# SCH_1.net
KiCad netlist of a schematic drawn in Altium Designer
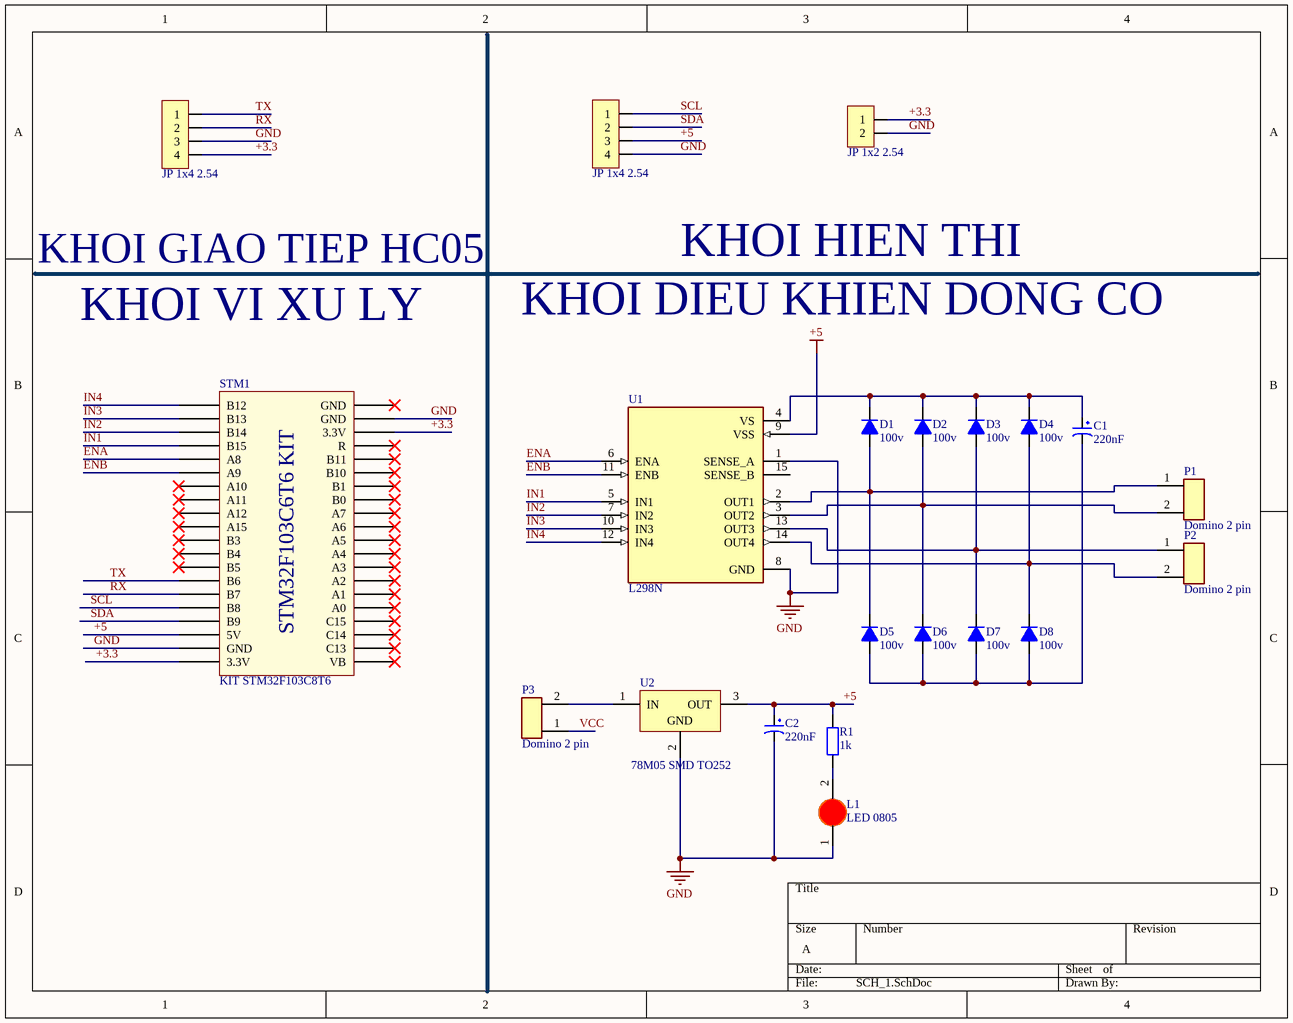
[diagram p0: SCH_1.SchDoc]

(export (version "E")
  (design (tool "Eeschema 10.0.6"))
  (components
    (comp (ref "C1")
      (value "220nF")
      (footprint "tu hoa 8mm")
      (description "Cắm")
      (libsource (lib "Altium_Lib_by_KhueNguyenCreator") (part "Tu Hoa 220uF 35V 8x12"))
    )
    (comp (ref "C2")
      (value "220nF")
      (footprint "tu hoa 8mm")
      (description "Cắm")
      (libsource (lib "Altium_Lib_by_KhueNguyenCreator") (part "Tu Hoa 220uF 35V 8x12"))
    )
    (comp (ref "D1")
      (value "100v")
      (footprint "DIODE 1A")
      (description "Cắm")
      (libsource (lib "Altium_Lib_by_KhueNguyenCreator") (part "Diode 1N4007"))
    )
    (comp (ref "D2")
      (value "100v")
      (footprint "DIODE 1A")
      (description "Cắm")
      (libsource (lib "Altium_Lib_by_KhueNguyenCreator") (part "Diode 1N4007"))
    )
    (comp (ref "D3")
      (value "100v")
      (footprint "DIODE 1A")
      (description "Cắm")
      (libsource (lib "Altium_Lib_by_KhueNguyenCreator") (part "Diode 1N4007"))
    )
    (comp (ref "D4")
      (value "100v")
      (footprint "DIODE 1A")
      (description "Cắm")
      (libsource (lib "Altium_Lib_by_KhueNguyenCreator") (part "Diode 1N4007"))
    )
    (comp (ref "D5")
      (value "100v")
      (footprint "DIODE 1A")
      (description "Cắm")
      (libsource (lib "Altium_Lib_by_KhueNguyenCreator") (part "Diode 1N4007"))
    )
    (comp (ref "D6")
      (value "100v")
      (footprint "DIODE 1A")
      (description "Cắm")
      (libsource (lib "Altium_Lib_by_KhueNguyenCreator") (part "Diode 1N4007"))
    )
    (comp (ref "D7")
      (value "100v")
      (footprint "DIODE 1A")
      (description "Cắm")
      (libsource (lib "Altium_Lib_by_KhueNguyenCreator") (part "Diode 1N4007"))
    )
    (comp (ref "D8")
      (value "100v")
      (footprint "DIODE 1A")
      (description "Cắm")
      (libsource (lib "Altium_Lib_by_KhueNguyenCreator") (part "Diode 1N4007"))
    )
    (comp (ref "JP1")
      (value "JP 1x4 2.54")
      (footprint "JP 1x4 CT")
      (description "Cắm")
      (libsource (lib "Altium_Lib_by_KhueNguyenCreator") (part "JP 1x4 2.54 Cai Thang"))
    )
    (comp (ref "JP2")
      (value "JP 1x4 2.54")
      (footprint "JP 1x4 CC")
      (description "Cắm")
      (libsource (lib "Altium_Lib_by_KhueNguyenCreator") (part "JP 1x4 2.54 Cai Cong"))
    )
    (comp (ref "JP3")
      (value "JP 1x2 2.54")
      (footprint "JP 1x2 DC")
      (description "Cắm")
      (libsource (lib "Altium_Lib_by_KhueNguyenCreator") (part "JP 1x2 2.54 Duc Cong"))
    )
    (comp (ref "L1")
      (value "LED 0805")
      (footprint "LED-0805-Red")
      (description "Dán")
      (libsource (lib "Altium_Lib_by_KhueNguyenCreator") (part "LED 0805 Do"))
    )
    (comp (ref "P1")
      (value "Domino 2 pin")
      (footprint "thuvien_altium:Domino_2pin_5.08mm")
      (description "domino 2 pin")
      (libsource (lib "thuvien_altium") (part "domino_2pin"))
    )
    (comp (ref "P2")
      (value "Domino 2 pin")
      (footprint "thuvien_altium:Domino_2pin_5.08mm")
      (description "domino 2 pin")
      (libsource (lib "thuvien_altium") (part "domino_2pin"))
    )
    (comp (ref "P3")
      (value "Domino 2 pin")
      (footprint "thuvien_altium:Domino_2pin_5.08mm")
      (description "domino 2 pin")
      (libsource (lib "") (part "domino_2pin_1"))
    )
    (comp (ref "R1")
      (value "1k")
      (footprint "tro smd 0805")
      (description "Dán")
      (libsource (lib "Altium_Lib_by_KhueNguyenCreator") (part "Tro 0805 5% 1k"))
    )
    (comp (ref "STM1")
      (value "KIT STM32F103C8T6")
      (footprint "STM32F103 KIT")
      (description "KIT STM32F103C8T6 Bluepill")
      (libsource (lib "Altium_Lib_by_KhueNguyenCreator") (part "STM32f103 Bluepill"))
    )
    (comp (ref "U1")
      (value "L298N")
      (footprint "L298N")
      (description "Half Bridge _4_ Driver DC Motors, Relays, Solenoids, Stepper Motors Bipolar 15-Multiwatt")
      (fields (field (name "MF") "STMicroelectronics"))
      (libsource (lib "Altium_Lib_by_KhueNguyenCreator") (part "L298N"))
    )
    (comp (ref "U2")
      (value "78M05 SMD TO252")
      (footprint "TO252")
      (description "Dán")
      (libsource (lib "Altium_Lib_by_KhueNguyenCreator") (part "78M05 SMD TO252"))
    )
  )
  (nets
    (net (code "1") (name "+5") (class "Default")
      (node (ref "C2") (pin "1") (pinfunction "1_1") (pintype "passive"))
      (node (ref "JP2") (pin "3") (pinfunction "3_3") (pintype "passive"))
      (node (ref "R1") (pin "2") (pinfunction "2_2") (pintype "passive"))
      (node (ref "STM1") (pin "18") (pinfunction "5V_18") (pintype "passive"))
      (node (ref "U1") (pin "9") (pinfunction "VSS_9") (pintype "input"))
      (node (ref "U2") (pin "3") (pinfunction "OUT_3") (pintype "power_in"))
    )
    (net (code "2") (name "/+3.3") (class "Default")
      (node (ref "JP1") (pin "4") (pinfunction "4_4") (pintype "passive"))
      (node (ref "JP3") (pin "1") (pinfunction "1_1") (pintype "passive"))
      (node (ref "STM1") (pin "20") (pinfunction "3.3V_20") (pintype "passive"))
      (node (ref "STM1") (pin "38") (pinfunction "3.3V_38") (pintype "passive"))
    )
    (net (code "3") (name "/ENA") (class "Default")
      (node (ref "STM1") (pin "5") (pinfunction "A8_5") (pintype "passive"))
      (node (ref "U1") (pin "6") (pinfunction "ENA_6") (pintype "input"))
    )
    (net (code "4") (name "/ENB") (class "Default")
      (node (ref "STM1") (pin "6") (pinfunction "A9_6") (pintype "passive"))
      (node (ref "U1") (pin "11") (pinfunction "ENB_11") (pintype "input"))
    )
    (net (code "5") (name "/IN1") (class "Default")
      (node (ref "STM1") (pin "4") (pinfunction "B15_4") (pintype "passive"))
      (node (ref "U1") (pin "5") (pinfunction "IN1_5") (pintype "input"))
    )
    (net (code "6") (name "/IN2") (class "Default")
      (node (ref "STM1") (pin "3") (pinfunction "B14_3") (pintype "passive"))
      (node (ref "U1") (pin "7") (pinfunction "IN2_7") (pintype "input"))
    )
    (net (code "7") (name "/IN3") (class "Default")
      (node (ref "STM1") (pin "2") (pinfunction "B13_2") (pintype "passive"))
      (node (ref "U1") (pin "10") (pinfunction "IN3_10") (pintype "input"))
    )
    (net (code "8") (name "/IN4") (class "Default")
      (node (ref "STM1") (pin "1") (pinfunction "B12_1") (pintype "passive"))
      (node (ref "U1") (pin "12") (pinfunction "IN4_12") (pintype "input"))
    )
    (net (code "9") (name "/RX") (class "Default")
      (node (ref "JP1") (pin "2") (pinfunction "2_2") (pintype "passive"))
      (node (ref "STM1") (pin "15") (pinfunction "B7_15") (pintype "passive"))
    )
    (net (code "10") (name "/SCL") (class "Default")
      (node (ref "JP2") (pin "1") (pinfunction "1_1") (pintype "passive"))
      (node (ref "STM1") (pin "16") (pinfunction "B8_16") (pintype "passive"))
    )
    (net (code "11") (name "/SDA") (class "Default")
      (node (ref "JP2") (pin "2") (pinfunction "2_2") (pintype "passive"))
      (node (ref "STM1") (pin "17") (pinfunction "B9_17") (pintype "passive"))
    )
    (net (code "12") (name "/TX") (class "Default")
      (node (ref "JP1") (pin "1") (pinfunction "1_1") (pintype "passive"))
      (node (ref "STM1") (pin "14") (pinfunction "B6_14") (pintype "passive"))
    )
    (net (code "13") (name "/VCC") (class "Default")
      (node (ref "P3") (pin "1") (pinfunction "1_1") (pintype "power_in"))
    )
    (net (code "14") (name "GND") (class "Default")
      (node (ref "C2") (pin "2") (pinfunction "2_2") (pintype "passive"))
      (node (ref "JP1") (pin "3") (pinfunction "3_3") (pintype "passive"))
      (node (ref "JP2") (pin "4") (pinfunction "4_4") (pintype "passive"))
      (node (ref "JP3") (pin "2") (pinfunction "2_2") (pintype "passive"))
      (node (ref "L1") (pin "1") (pinfunction "A_1") (pintype "passive"))
      (node (ref "STM1") (pin "19") (pinfunction "GND_19") (pintype "passive"))
      (node (ref "STM1") (pin "39") (pinfunction "GND_39") (pintype "passive"))
      (node (ref "U1") (pin "1") (pinfunction "SENSE_A_1") (pintype "passive"))
      (node (ref "U1") (pin "8") (pinfunction "GND_8") (pintype "power_in"))
      (node (ref "U2") (pin "2") (pinfunction "GND_2") (pintype "power_in"))
    )
    (net (code "15") (name "Net-(D1-A)") (class "Default")
      (node (ref "D1") (pin "1") (pinfunction "A_1") (pintype "passive"))
      (node (ref "D5") (pin "2") (pinfunction "K_2") (pintype "passive"))
      (node (ref "P1") (pin "1") (pinfunction "1_1") (pintype "power_in"))
      (node (ref "U1") (pin "2") (pinfunction "OUT1_2") (pintype "output"))
    )
    (net (code "16") (name "Net-(D1-K)") (class "Default")
      (node (ref "C1") (pin "1") (pinfunction "1_1") (pintype "passive"))
      (node (ref "D1") (pin "2") (pinfunction "K_2") (pintype "passive"))
      (node (ref "D2") (pin "2") (pinfunction "K_2") (pintype "passive"))
      (node (ref "D3") (pin "2") (pinfunction "K_2") (pintype "passive"))
      (node (ref "D4") (pin "2") (pinfunction "K_2") (pintype "passive"))
      (node (ref "U1") (pin "4") (pinfunction "VS_4") (pintype "power_in"))
    )
    (net (code "17") (name "Net-(D2-A)") (class "Default")
      (node (ref "D2") (pin "1") (pinfunction "A_1") (pintype "passive"))
      (node (ref "D6") (pin "2") (pinfunction "K_2") (pintype "passive"))
      (node (ref "P1") (pin "2") (pinfunction "2_2") (pintype "power_in"))
      (node (ref "U1") (pin "3") (pinfunction "OUT2_3") (pintype "output"))
    )
    (net (code "18") (name "Net-(D3-A)") (class "Default")
      (node (ref "D3") (pin "1") (pinfunction "A_1") (pintype "passive"))
      (node (ref "D7") (pin "2") (pinfunction "K_2") (pintype "passive"))
      (node (ref "P2") (pin "1") (pinfunction "1_1") (pintype "power_in"))
      (node (ref "U1") (pin "13") (pinfunction "OUT3_13") (pintype "output"))
    )
    (net (code "19") (name "Net-(D4-A)") (class "Default")
      (node (ref "D4") (pin "1") (pinfunction "A_1") (pintype "passive"))
      (node (ref "D8") (pin "2") (pinfunction "K_2") (pintype "passive"))
      (node (ref "P2") (pin "2") (pinfunction "2_2") (pintype "power_in"))
      (node (ref "U1") (pin "14") (pinfunction "OUT4_14") (pintype "output"))
    )
    (net (code "20") (name "Net-(D5-A)") (class "Default")
      (node (ref "C1") (pin "2") (pinfunction "2_2") (pintype "passive"))
      (node (ref "D5") (pin "1") (pinfunction "A_1") (pintype "passive"))
      (node (ref "D6") (pin "1") (pinfunction "A_1") (pintype "passive"))
      (node (ref "D7") (pin "1") (pinfunction "A_1") (pintype "passive"))
      (node (ref "D8") (pin "1") (pinfunction "A_1") (pintype "passive"))
    )
    (net (code "21") (name "Net-(L1-K)") (class "Default")
      (node (ref "L1") (pin "2") (pinfunction "K_2") (pintype "passive"))
      (node (ref "R1") (pin "1") (pinfunction "1_1") (pintype "passive"))
    )
    (net (code "22") (name "Net-(U2-IN)") (class "Default")
      (node (ref "P3") (pin "2") (pinfunction "2_2") (pintype "power_in"))
      (node (ref "U2") (pin "1") (pinfunction "IN_1") (pintype "power_in"))
    )
    (net (code "23") (name "unconnected-(STM1-A0-Pad25)") (class "Default")
      (node (ref "STM1") (pin "25") (pinfunction "A0_25") (pintype "passive+no_connect"))
    )
    (net (code "24") (name "unconnected-(STM1-A1-Pad26)") (class "Default")
      (node (ref "STM1") (pin "26") (pinfunction "A1_26") (pintype "passive+no_connect"))
    )
    (net (code "25") (name "unconnected-(STM1-A2-Pad27)") (class "Default")
      (node (ref "STM1") (pin "27") (pinfunction "A2_27") (pintype "passive+no_connect"))
    )
    (net (code "26") (name "unconnected-(STM1-A3-Pad28)") (class "Default")
      (node (ref "STM1") (pin "28") (pinfunction "A3_28") (pintype "passive+no_connect"))
    )
    (net (code "27") (name "unconnected-(STM1-A4-Pad29)") (class "Default")
      (node (ref "STM1") (pin "29") (pinfunction "A4_29") (pintype "passive+no_connect"))
    )
    (net (code "28") (name "unconnected-(STM1-A5-Pad30)") (class "Default")
      (node (ref "STM1") (pin "30") (pinfunction "A5_30") (pintype "passive+no_connect"))
    )
    (net (code "29") (name "unconnected-(STM1-A6-Pad31)") (class "Default")
      (node (ref "STM1") (pin "31") (pinfunction "A6_31") (pintype "passive+no_connect"))
    )
    (net (code "30") (name "unconnected-(STM1-A7-Pad32)") (class "Default")
      (node (ref "STM1") (pin "32") (pinfunction "A7_32") (pintype "passive+no_connect"))
    )
    (net (code "31") (name "unconnected-(STM1-A10-Pad7)") (class "Default")
      (node (ref "STM1") (pin "7") (pinfunction "A10_7") (pintype "passive+no_connect"))
    )
    (net (code "32") (name "unconnected-(STM1-A11-Pad8)") (class "Default")
      (node (ref "STM1") (pin "8") (pinfunction "A11_8") (pintype "passive+no_connect"))
    )
    (net (code "33") (name "unconnected-(STM1-A12-Pad9)") (class "Default")
      (node (ref "STM1") (pin "9") (pinfunction "A12_9") (pintype "passive+no_connect"))
    )
    (net (code "34") (name "unconnected-(STM1-A15-Pad10)") (class "Default")
      (node (ref "STM1") (pin "10") (pinfunction "A15_10") (pintype "passive+no_connect"))
    )
    (net (code "35") (name "unconnected-(STM1-B0-Pad33)") (class "Default")
      (node (ref "STM1") (pin "33") (pinfunction "B0_33") (pintype "passive+no_connect"))
    )
    (net (code "36") (name "unconnected-(STM1-B1-Pad34)") (class "Default")
      (node (ref "STM1") (pin "34") (pinfunction "B1_34") (pintype "passive+no_connect"))
    )
    (net (code "37") (name "unconnected-(STM1-B3-Pad11)") (class "Default")
      (node (ref "STM1") (pin "11") (pinfunction "B3_11") (pintype "passive+no_connect"))
    )
    (net (code "38") (name "unconnected-(STM1-B4-Pad12)") (class "Default")
      (node (ref "STM1") (pin "12") (pinfunction "B4_12") (pintype "passive+no_connect"))
    )
    (net (code "39") (name "unconnected-(STM1-B5-Pad13)") (class "Default")
      (node (ref "STM1") (pin "13") (pinfunction "B5_13") (pintype "passive+no_connect"))
    )
    (net (code "40") (name "unconnected-(STM1-B10-Pad35)") (class "Default")
      (node (ref "STM1") (pin "35") (pinfunction "B10_35") (pintype "passive+no_connect"))
    )
    (net (code "41") (name "unconnected-(STM1-B11-Pad36)") (class "Default")
      (node (ref "STM1") (pin "36") (pinfunction "B11_36") (pintype "passive+no_connect"))
    )
    (net (code "42") (name "unconnected-(STM1-C13-Pad22)") (class "Default")
      (node (ref "STM1") (pin "22") (pinfunction "C13_22") (pintype "passive+no_connect"))
    )
    (net (code "43") (name "unconnected-(STM1-C14-Pad23)") (class "Default")
      (node (ref "STM1") (pin "23") (pinfunction "C14_23") (pintype "passive+no_connect"))
    )
    (net (code "44") (name "unconnected-(STM1-C15-Pad24)") (class "Default")
      (node (ref "STM1") (pin "24") (pinfunction "C15_24") (pintype "passive+no_connect"))
    )
    (net (code "45") (name "unconnected-(STM1-GND-Pad40)") (class "Default")
      (node (ref "STM1") (pin "40") (pinfunction "GND_40") (pintype "passive+no_connect"))
    )
    (net (code "46") (name "unconnected-(STM1-R-Pad37)") (class "Default")
      (node (ref "STM1") (pin "37") (pinfunction "R_37") (pintype "passive+no_connect"))
    )
    (net (code "47") (name "unconnected-(STM1-VB-Pad21)") (class "Default")
      (node (ref "STM1") (pin "21") (pinfunction "VB_21") (pintype "passive+no_connect"))
    )
    (net (code "48") (name "unconnected-(U1-SENSE_B-Pad15)") (class "Default")
      (node (ref "U1") (pin "15") (pinfunction "SENSE_B_15") (pintype "passive"))
    )
  )
)
